# 01-SOM.net
KiCad netlist of a schematic drawn in Altium Designer
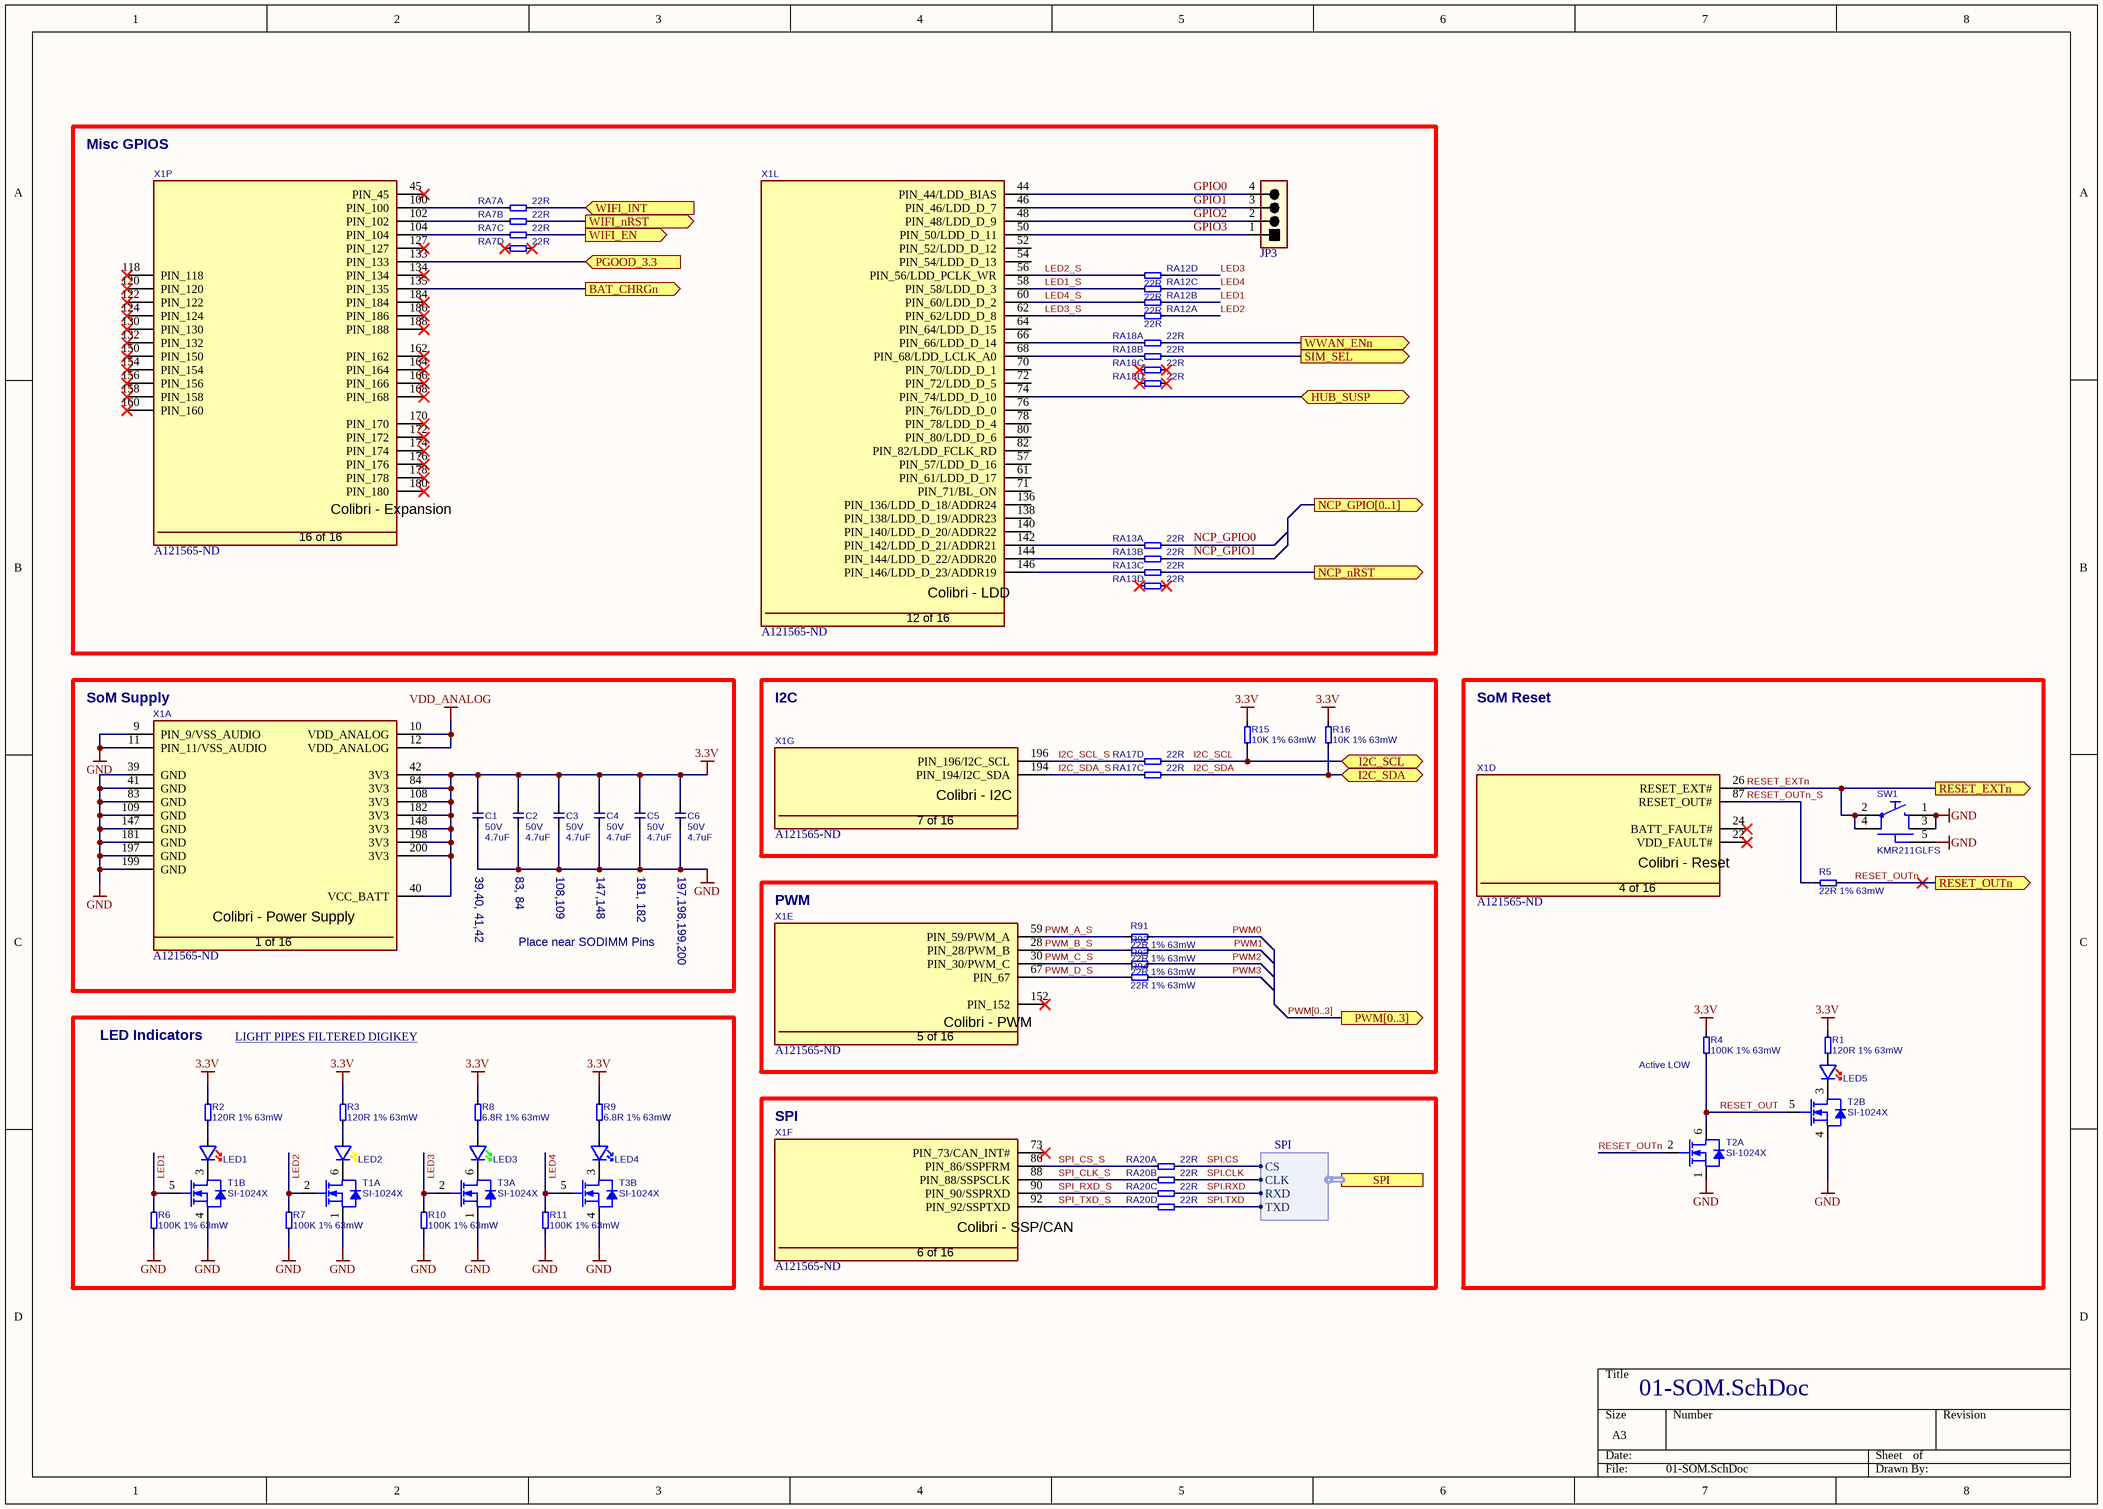
[diagram p0: 01-SOM.SchDoc]

(export (version "E")
  (design (tool "Eeschema 10.0.6"))
  (components
    (comp (ref "C1")
      (value "4.7uF")
      (footprint "T_CAPC1206X180N")
      (description "Capacitor Ceramic X7R 4.7uF 50V 20% 1206")
      (fields
        (field (name "TOLERANCE") "10%")
        (field (name "RATING") "50V")
        (field (name "Comment") "4.7uF 50V 20% X7R")
      )
      (libsource (lib "AI Gateway - Carrier") (part "C-4.7uF-50V-20%-1210"))
    )
    (comp (ref "C2")
      (value "4.7uF")
      (footprint "T_CAPC1206X180N")
      (description "Capacitor Ceramic X7R 4.7uF 50V 20% 1206")
      (fields
        (field (name "TOLERANCE") "10%")
        (field (name "RATING") "50V")
        (field (name "Comment") "4.7uF 50V 20% X7R")
      )
      (libsource (lib "AI Gateway - Carrier") (part "C-4.7uF-50V-20%-1210"))
    )
    (comp (ref "C3")
      (value "4.7uF")
      (footprint "T_CAPC1206X180N")
      (description "Capacitor Ceramic X7R 4.7uF 50V 20% 1206")
      (fields
        (field (name "TOLERANCE") "10%")
        (field (name "RATING") "50V")
        (field (name "Comment") "4.7uF 50V 20% X7R")
      )
      (libsource (lib "AI Gateway - Carrier") (part "C-4.7uF-50V-20%-1210"))
    )
    (comp (ref "C4")
      (value "4.7uF")
      (footprint "T_CAPC1206X180N")
      (description "Capacitor Ceramic X7R 4.7uF 50V 20% 1206")
      (fields
        (field (name "TOLERANCE") "10%")
        (field (name "RATING") "50V")
        (field (name "Comment") "4.7uF 50V 20% X7R")
      )
      (libsource (lib "AI Gateway - Carrier") (part "C-4.7uF-50V-20%-1210"))
    )
    (comp (ref "C5")
      (value "4.7uF")
      (footprint "T_CAPC1206X180N")
      (description "Capacitor Ceramic X7R 4.7uF 50V 20% 1206")
      (fields
        (field (name "TOLERANCE") "10%")
        (field (name "RATING") "50V")
        (field (name "Comment") "4.7uF 50V 20% X7R")
      )
      (libsource (lib "AI Gateway - Carrier") (part "C-4.7uF-50V-20%-1210"))
    )
    (comp (ref "C6")
      (value "4.7uF")
      (footprint "T_CAPC1206X180N")
      (description "Capacitor Ceramic X7R 4.7uF 50V 20% 1206")
      (fields
        (field (name "TOLERANCE") "10%")
        (field (name "RATING") "50V")
        (field (name "Comment") "4.7uF 50V 20% X7R")
      )
      (libsource (lib "AI Gateway - Carrier") (part "C-4.7uF-50V-20%-1210"))
    )
    (comp (ref "JP3")
      (value "61300411121")
      (footprint "Header 1x4, 2.54mm pitch, male")
      (description "Header male, 1x4 Pins, 2.54 mm pitch")
      (fields (field (name "MFG") "Würth Elektronik"))
      (libsource (lib "AI Gateway - Carrier") (part "Header 1x4"))
    )
    (comp (ref "LED1")
      (value "150060RS75000")
      (footprint "LEDC1608X80N")
      (description "Red 625nm LED Indication - Discrete 2V 0603 (1608 Metric)")
      (fields (field (name "MFG") "Würth Elektronik"))
      (libsource (lib "AI Gateway - Carrier") (part "LED-RED-0603"))
    )
    (comp (ref "LED2")
      (value "150060YS75000")
      (footprint "LEDC1608X80N")
      (description "Yellow 590nm LED Indication - Discrete 2V 0603 (1608 Metric)")
      (fields (field (name "MFG") "Würth Elektronik"))
      (libsource (lib "AI Gateway - Carrier") (part "LED-YELLOW-0603"))
    )
    (comp (ref "LED3")
      (value "150060GS75000")
      (footprint "LEDC1608X80N")
      (description "Green 520nm LED Indication - Discrete 3.2V 0603 (1608 Metric)")
      (fields (field (name "MFG") "Würth Elektronik"))
      (libsource (lib "AI Gateway - Carrier") (part "LED-GREEN-0603"))
    )
    (comp (ref "LED4")
      (value "150060BS75000")
      (footprint "LEDC1608X80N")
      (description "Blue 470nm LED Indication - Discrete 3.2V 0603 (1608 Metric)")
      (fields (field (name "MFG") "Würth Elektronik"))
      (libsource (lib "AI Gateway - Carrier") (part "LED-BLUE-0603"))
    )
    (comp (ref "LED5")
      (value "150060RS75000")
      (footprint "LEDC1608X80N")
      (description "Red 625nm LED Indication - Discrete 2V 0603 (1608 Metric)")
      (fields (field (name "MFG") "Würth Elektronik"))
      (libsource (lib "AI Gateway - Carrier") (part "LED-RED-0603"))
    )
    (comp (ref "R1")
      (value "120R 1% 63mW")
      (footprint "RESC1005X40N")
      (description "Resistor 120ohm 63mW 1% 0402")
      (fields (field (name "POWER") "63mW") (field (name "TOLERANCE") "1%"))
      (libsource (lib "AI Gateway - Carrier") (part "R-120R-1%-0402"))
    )
    (comp (ref "R2")
      (value "120R 1% 63mW")
      (footprint "RESC1005X40N")
      (description "Resistor 120ohm 63mW 1% 0402")
      (fields (field (name "POWER") "63mW") (field (name "TOLERANCE") "1%"))
      (libsource (lib "AI Gateway - Carrier") (part "R-120R-1%-0402"))
    )
    (comp (ref "R3")
      (value "120R 1% 63mW")
      (footprint "RESC1005X40N")
      (description "Resistor 120ohm 63mW 1% 0402")
      (fields (field (name "POWER") "63mW") (field (name "TOLERANCE") "1%"))
      (libsource (lib "AI Gateway - Carrier") (part "R-120R-1%-0402"))
    )
    (comp (ref "R4")
      (value "100K 1% 63mW")
      (footprint "RESC1005X40N")
      (description "Resistor 100Kohm 63mW 1% 0402")
      (fields (field (name "POWER") "63mW") (field (name "TOLERANCE") "1%"))
      (libsource (lib "AI Gateway - Carrier") (part "R-100K-1%-0402"))
    )
    (comp (ref "R5")
      (value "22R 1% 63mW")
      (footprint "RESC1005X40N")
      (description "Resistor 22ohm 63mW 1% 0402")
      (fields (field (name "POWER") "63mW") (field (name "TOLERANCE") "1%"))
      (libsource (lib "AI Gateway - Carrier") (part "R-22R-1%-0402"))
    )
    (comp (ref "R6")
      (value "100K 1% 63mW")
      (footprint "RESC1005X40N")
      (description "Resistor 100Kohm 63mW 1% 0402")
      (fields (field (name "TOLERANCE") "1%") (field (name "POWER") "63mW"))
      (libsource (lib "AI Gateway - Carrier") (part "R-100K-1%-0402"))
    )
    (comp (ref "R7")
      (value "100K 1% 63mW")
      (footprint "RESC1005X40N")
      (description "Resistor 100Kohm 63mW 1% 0402")
      (fields (field (name "TOLERANCE") "1%") (field (name "POWER") "63mW"))
      (libsource (lib "AI Gateway - Carrier") (part "R-100K-1%-0402"))
    )
    (comp (ref "R8")
      (value "6.8R 1% 63mW")
      (footprint "RESC1005X40N")
      (description "Resistor 6.8ohm 63mW 1% 0402")
      (fields (field (name "POWER") "63mW") (field (name "TOLERANCE") "1%"))
      (libsource (lib "AI Gateway - Carrier") (part "R-6.8R-1%-0402"))
    )
    (comp (ref "R9")
      (value "6.8R 1% 63mW")
      (footprint "RESC1005X40N")
      (description "Resistor 6.8ohm 63mW 1% 0402")
      (fields (field (name "POWER") "63mW") (field (name "TOLERANCE") "1%"))
      (libsource (lib "AI Gateway - Carrier") (part "R-6.8R-1%-0402"))
    )
    (comp (ref "R10")
      (value "100K 1% 63mW")
      (footprint "RESC1005X40N")
      (description "Resistor 100Kohm 63mW 1% 0402")
      (fields (field (name "TOLERANCE") "1%") (field (name "POWER") "63mW"))
      (libsource (lib "AI Gateway - Carrier") (part "R-100K-1%-0402"))
    )
    (comp (ref "R11")
      (value "100K 1% 63mW")
      (footprint "RESC1005X40N")
      (description "Resistor 100Kohm 63mW 1% 0402")
      (fields (field (name "TOLERANCE") "1%") (field (name "POWER") "63mW"))
      (libsource (lib "AI Gateway - Carrier") (part "R-100K-1%-0402"))
    )
    (comp (ref "R15")
      (value "10K 1% 63mW")
      (footprint "RESC1005X40N")
      (description "Resistor 10Kohm 63mW 1% 0402")
      (fields (field (name "POWER") "63mW") (field (name "TOLERANCE") "1%"))
      (libsource (lib "AI Gateway - Carrier") (part "R-10K-1%-0402"))
    )
    (comp (ref "R16")
      (value "10K 1% 63mW")
      (footprint "RESC1005X40N")
      (description "Resistor 10Kohm 63mW 1% 0402")
      (fields (field (name "POWER") "63mW") (field (name "TOLERANCE") "1%"))
      (libsource (lib "AI Gateway - Carrier") (part "R-10K-1%-0402"))
    )
    (comp (ref "R91")
      (value "22R 1% 63mW")
      (footprint "RESC1005X40N")
      (description "Resistor 22ohm 63mW 1% 0402")
      (fields (field (name "POWER") "63mW") (field (name "TOLERANCE") "1%"))
      (libsource (lib "AI Gateway - Carrier") (part "R-22R-1%-0402"))
    )
    (comp (ref "R92")
      (value "22R 1% 63mW")
      (footprint "RESC1005X40N")
      (description "Resistor 22ohm 63mW 1% 0402")
      (fields (field (name "POWER") "63mW") (field (name "TOLERANCE") "1%"))
      (libsource (lib "AI Gateway - Carrier") (part "R-22R-1%-0402"))
    )
    (comp (ref "R93")
      (value "22R 1% 63mW")
      (footprint "RESC1005X40N")
      (description "Resistor 22ohm 63mW 1% 0402")
      (fields (field (name "POWER") "63mW") (field (name "TOLERANCE") "1%"))
      (libsource (lib "AI Gateway - Carrier") (part "R-22R-1%-0402"))
    )
    (comp (ref "R94")
      (value "22R 1% 63mW")
      (footprint "RESC1005X40N")
      (description "Resistor 22ohm 63mW 1% 0402")
      (fields (field (name "POWER") "63mW") (field (name "TOLERANCE") "1%"))
      (libsource (lib "AI Gateway - Carrier") (part "R-22R-1%-0402"))
    )
    (comp (ref "RA7")
      (value "22R")
      (footprint "T_Resistor_Array_X4")
      (description "Resistor Array 22 R 63mW 5% 1206")
      (fields (field (name "TOLERANCE") "5%") (field (name "MFG") "Generic"))
      (libsource (lib "Passive") (part "RA-22R-5%-1206-div"))
    )
    (comp (ref "RA12")
      (value "22R")
      (footprint "T_Resistor_Array_X4")
      (description "Resistor Array 22 R 63mW 5% 1206")
      (fields (field (name "TOLERANCE") "5%") (field (name "MFG") "Generic"))
      (libsource (lib "Passive") (part "RA-22R-5%-1206-div"))
    )
    (comp (ref "RA13")
      (value "22R")
      (footprint "T_Resistor_Array_X4")
      (description "Resistor Array 22 R 63mW 5% 1206")
      (fields (field (name "TOLERANCE") "5%") (field (name "MFG") "Generic"))
      (libsource (lib "Passive") (part "RA-22R-5%-1206-div"))
    )
    (comp (ref "RA17")
      (value "22R")
      (footprint "T_Resistor_Array_X4")
      (description "Resistor Array 22 R 63mW 5% 1206")
      (fields (field (name "TOLERANCE") "5%") (field (name "MFG") "Generic"))
      (libsource (lib "Passive") (part "RA-22R-5%-1206-div"))
    )
    (comp (ref "RA18")
      (value "22R")
      (footprint "T_Resistor_Array_X4")
      (description "Resistor Array 22 R 63mW 5% 1206")
      (fields (field (name "TOLERANCE") "5%") (field (name "MFG") "Generic"))
      (libsource (lib "Passive") (part "RA-22R-5%-1206-div"))
    )
    (comp (ref "RA20")
      (value "22R")
      (footprint "T_Resistor_Array_X4")
      (description "Resistor Array 22 R 63mW 5% 1206")
      (fields (field (name "TOLERANCE") "5%") (field (name "MFG") "Generic"))
      (libsource (lib "Passive") (part "RA-22R-5%-1206-div"))
    )
    (comp (ref "SW1")
      (value "KMR211GLFS")
      (footprint "T_CnK_KMR211GLFS")
      (description "Power ON Switch")
      (fields (field (name "MFG") "C&N"))
      (libsource (lib "Passive") (part "SW-KMR211GLFS-1VA"))
    )
    (comp (ref "T1")
      (value "SI-1024X")
      (footprint "SOTFL50P160X60-6N")
      (description "Mosfet Array 2 N-Channel (Dual) 20V 485mA 250mW Surface Mount SC-89-6")
      (fields (field (name "MFG") "Vishay"))
      (libsource (lib "AI Gateway - Carrier") (part "T-Vishay-SI-1024X"))
    )
    (comp (ref "T2")
      (value "SI-1024X")
      (footprint "SOTFL50P160X60-6N")
      (description "Mosfet Array 2 N-Channel (Dual) 20V 485mA 250mW Surface Mount SC-89-6")
      (fields (field (name "MFG") "Vishay"))
      (libsource (lib "AI Gateway - Carrier") (part "T-Vishay-SI-1024X"))
    )
    (comp (ref "T3")
      (value "SI-1024X")
      (footprint "SOTFL50P160X60-6N")
      (description "Mosfet Array 2 N-Channel (Dual) 20V 485mA 250mW Surface Mount SC-89-6")
      (fields (field (name "MFG") "Vishay"))
      (libsource (lib "AI Gateway - Carrier") (part "T-Vishay-SI-1024X"))
    )
    (comp (ref "X1")
      (value "1473005-1")
      (footprint "T_Tyco_1473005-1")
      (description "SODIMM Connector")
      (fields (field (name "SUPPLIER PART NUMBER 1") "A121565-ND"))
      (libsource (lib "Connectors") (part "CON-Tyco-1473005-1-200-0.6mm"))
    )
  )
  (nets
    (net (code "2") (name "/BAT_CHRGn") (class "Default")
      (node (ref "X1") (pin "135") (pinfunction "PIN_135_135") (pintype "passive"))
    )
    (net (code "3") (name "/GPIO0") (class "Default")
      (node (ref "JP3") (pin "4") (pinfunction "4_4") (pintype "passive"))
      (node (ref "X1") (pin "44") (pinfunction "PIN_44/LDD_BIAS_44") (pintype "passive"))
    )
    (net (code "4") (name "/GPIO1") (class "Default")
      (node (ref "JP3") (pin "3") (pinfunction "3_3") (pintype "passive"))
      (node (ref "X1") (pin "46") (pinfunction "PIN_46/LDD_D_7_46") (pintype "passive"))
    )
    (net (code "5") (name "/GPIO2") (class "Default")
      (node (ref "JP3") (pin "2") (pinfunction "2_2") (pintype "passive"))
      (node (ref "X1") (pin "48") (pinfunction "PIN_48/LDD_D_9_48") (pintype "passive"))
    )
    (net (code "6") (name "/GPIO3") (class "Default")
      (node (ref "JP3") (pin "1") (pinfunction "1_1") (pintype "passive"))
      (node (ref "X1") (pin "50") (pinfunction "PIN_50/LDD_D_11_50") (pintype "passive"))
    )
    (net (code "7") (name "/HUB_SUSP") (class "Default")
      (node (ref "X1") (pin "74") (pinfunction "PIN_74/LDD_D_10_74") (pintype "passive"))
    )
    (net (code "8") (name "/I2C_SCL") (class "Default")
      (node (ref "R15") (pin "1") (pinfunction "1_1") (pintype "passive"))
      (node (ref "RA17") (pin "8") (pinfunction "8_8") (pintype "passive"))
    )
    (net (code "9") (name "/I2C_SCL_S") (class "Default")
      (node (ref "RA17") (pin "4") (pinfunction "4_4") (pintype "passive"))
      (node (ref "X1") (pin "196") (pinfunction "PIN_196/I2C_SCL_196") (pintype "passive"))
    )
    (net (code "10") (name "/I2C_SDA") (class "Default")
      (node (ref "R16") (pin "1") (pinfunction "1_1") (pintype "passive"))
      (node (ref "RA17") (pin "7") (pinfunction "7_7") (pintype "passive"))
    )
    (net (code "11") (name "/I2C_SDA_S") (class "Default")
      (node (ref "RA17") (pin "3") (pinfunction "3_3") (pintype "passive"))
      (node (ref "X1") (pin "194") (pinfunction "PIN_194/I2C_SDA_194") (pintype "passive"))
    )
    (net (code "12") (name "/LED1") (class "Default")
      (node (ref "R6") (pin "1") (pinfunction "1_1") (pintype "passive"))
      (node (ref "RA12") (pin "2") (pinfunction "2_2") (pintype "passive"))
      (node (ref "T1") (pin "5") (pinfunction "G_5") (pintype "passive"))
    )
    (net (code "13") (name "/LED1_S") (class "Default")
      (node (ref "RA12") (pin "7") (pinfunction "7_7") (pintype "passive"))
      (node (ref "X1") (pin "58") (pinfunction "PIN_58/LDD_D_3_58") (pintype "passive"))
    )
    (net (code "14") (name "/LED2") (class "Default")
      (node (ref "R7") (pin "1") (pinfunction "1_1") (pintype "passive"))
      (node (ref "RA12") (pin "1") (pinfunction "1_1") (pintype "passive"))
      (node (ref "T1") (pin "2") (pinfunction "G_2") (pintype "passive"))
    )
    (net (code "15") (name "/LED2_S") (class "Default")
      (node (ref "RA12") (pin "8") (pinfunction "8_8") (pintype "passive"))
      (node (ref "X1") (pin "56") (pinfunction "PIN_56/LDD_PCLK_WR_56") (pintype "passive"))
    )
    (net (code "16") (name "/LED3") (class "Default")
      (node (ref "R10") (pin "1") (pinfunction "1_1") (pintype "passive"))
      (node (ref "RA12") (pin "4") (pinfunction "4_4") (pintype "passive"))
      (node (ref "T3") (pin "2") (pinfunction "G_2") (pintype "passive"))
    )
    (net (code "17") (name "/LED3_S") (class "Default")
      (node (ref "RA12") (pin "5") (pinfunction "5_5") (pintype "passive"))
      (node (ref "X1") (pin "62") (pinfunction "PIN_62/LDD_D_8_62") (pintype "passive"))
    )
    (net (code "18") (name "/LED4") (class "Default")
      (node (ref "R11") (pin "1") (pinfunction "1_1") (pintype "passive"))
      (node (ref "RA12") (pin "3") (pinfunction "3_3") (pintype "passive"))
      (node (ref "T3") (pin "5") (pinfunction "G_5") (pintype "passive"))
    )
    (net (code "19") (name "/LED4_S") (class "Default")
      (node (ref "RA12") (pin "6") (pinfunction "6_6") (pintype "passive"))
      (node (ref "X1") (pin "60") (pinfunction "PIN_60/LDD_D_2_60") (pintype "passive"))
    )
    (net (code "20") (name "/NCP_GPIO0") (class "Default")
      (node (ref "RA13") (pin "5") (pinfunction "5_5") (pintype "passive"))
    )
    (net (code "21") (name "/NCP_GPIO1") (class "Default")
      (node (ref "RA13") (pin "6") (pinfunction "6_6") (pintype "passive"))
    )
    (net (code "23") (name "/NCP_nRST") (class "Default")
      (node (ref "RA13") (pin "7") (pinfunction "7_7") (pintype "passive"))
    )
    (net (code "24") (name "/PGOOD_3.3") (class "Default")
      (node (ref "X1") (pin "133") (pinfunction "PIN_133_133") (pintype "passive"))
    )
    (net (code "25") (name "/PWM0") (class "Default")
      (node (ref "R91") (pin "1") (pinfunction "1_1") (pintype "passive"))
    )
    (net (code "26") (name "/PWM1") (class "Default")
      (node (ref "R92") (pin "1") (pinfunction "1_1") (pintype "passive"))
    )
    (net (code "27") (name "/PWM2") (class "Default")
      (node (ref "R93") (pin "1") (pinfunction "1_1") (pintype "passive"))
    )
    (net (code "28") (name "/PWM3") (class "Default")
      (node (ref "R94") (pin "1") (pinfunction "1_1") (pintype "passive"))
    )
    (net (code "30") (name "/PWM_A_S") (class "Default")
      (node (ref "R91") (pin "2") (pinfunction "2_2") (pintype "passive"))
      (node (ref "X1") (pin "59") (pinfunction "PIN_59/PWM_A_59") (pintype "passive"))
    )
    (net (code "31") (name "/PWM_B_S") (class "Default")
      (node (ref "R92") (pin "2") (pinfunction "2_2") (pintype "passive"))
      (node (ref "X1") (pin "28") (pinfunction "PIN_28/PWM_B_28") (pintype "passive"))
    )
    (net (code "32") (name "/PWM_C_S") (class "Default")
      (node (ref "R93") (pin "2") (pinfunction "2_2") (pintype "passive"))
      (node (ref "X1") (pin "30") (pinfunction "PIN_30/PWM_C_30") (pintype "passive"))
    )
    (net (code "33") (name "/PWM_D_S") (class "Default")
      (node (ref "R94") (pin "2") (pinfunction "2_2") (pintype "passive"))
      (node (ref "X1") (pin "67") (pinfunction "PIN_67_67") (pintype "passive"))
    )
    (net (code "34") (name "/RESET_EXTn") (class "Default")
      (node (ref "SW1") (pin "2") (pinfunction "2_2") (pintype "passive"))
      (node (ref "SW1") (pin "4") (pinfunction "4_4") (pintype "passive"))
      (node (ref "X1") (pin "26") (pinfunction "RESET_EXT#_26") (pintype "passive"))
    )
    (net (code "35") (name "/RESET_OUT") (class "Default")
      (node (ref "R4") (pin "1") (pinfunction "1_1") (pintype "passive"))
      (node (ref "T2") (pin "5") (pinfunction "G_5") (pintype "passive"))
      (node (ref "T2") (pin "6") (pinfunction "D_6") (pintype "passive"))
    )
    (net (code "36") (name "/RESET_OUTn") (class "Default")
      (node (ref "R5") (pin "1") (pinfunction "1_1") (pintype "passive"))
      (node (ref "T2") (pin "2") (pinfunction "G_2") (pintype "passive"))
    )
    (net (code "37") (name "/RESET_OUTn_S") (class "Default")
      (node (ref "R5") (pin "2") (pinfunction "2_2") (pintype "passive"))
      (node (ref "X1") (pin "87") (pinfunction "RESET_OUT#_87") (pintype "passive"))
    )
    (net (code "38") (name "/SIM_SEL") (class "Default")
      (node (ref "RA18") (pin "6") (pinfunction "6_6") (pintype "passive"))
    )
    (net (code "39") (name "/SPI.CLK") (class "Default")
      (node (ref "RA20") (pin "6") (pinfunction "6_6") (pintype "passive"))
    )
    (net (code "40") (name "/SPI.CS") (class "Default")
      (node (ref "RA20") (pin "5") (pinfunction "5_5") (pintype "passive"))
    )
    (net (code "41") (name "/SPI.RXD") (class "Default")
      (node (ref "RA20") (pin "7") (pinfunction "7_7") (pintype "passive"))
    )
    (net (code "42") (name "/SPI.TXD") (class "Default")
      (node (ref "RA20") (pin "8") (pinfunction "8_8") (pintype "passive"))
    )
    (net (code "43") (name "/SPI_CLK_S") (class "Default")
      (node (ref "RA20") (pin "2") (pinfunction "2_2") (pintype "passive"))
      (node (ref "X1") (pin "88") (pinfunction "PIN_88/SSPSCLK_88") (pintype "passive"))
    )
    (net (code "44") (name "/SPI_CS_S") (class "Default")
      (node (ref "RA20") (pin "1") (pinfunction "1_1") (pintype "passive"))
      (node (ref "X1") (pin "86") (pinfunction "PIN_86/SSPFRM_86") (pintype "passive"))
    )
    (net (code "45") (name "/SPI_RXD_S") (class "Default")
      (node (ref "RA20") (pin "3") (pinfunction "3_3") (pintype "passive"))
      (node (ref "X1") (pin "90") (pinfunction "PIN_90/SSPRXD_90") (pintype "passive"))
    )
    (net (code "46") (name "/SPI_TXD_S") (class "Default")
      (node (ref "RA20") (pin "4") (pinfunction "4_4") (pintype "passive"))
      (node (ref "X1") (pin "92") (pinfunction "PIN_92/SSPTXD_92") (pintype "passive"))
    )
    (net (code "47") (name "/WIFI_EN") (class "Default")
      (node (ref "RA7") (pin "7") (pinfunction "7_7") (pintype "passive"))
    )
    (net (code "48") (name "/WIFI_INT") (class "Default")
      (node (ref "RA7") (pin "5") (pinfunction "5_5") (pintype "passive"))
    )
    (net (code "49") (name "/WIFI_nRST") (class "Default")
      (node (ref "RA7") (pin "6") (pinfunction "6_6") (pintype "passive"))
    )
    (net (code "50") (name "/WWAN_ENn") (class "Default")
      (node (ref "RA18") (pin "5") (pinfunction "5_5") (pintype "passive"))
    )
    (net (code "52") (name "3.3V") (class "Default")
      (node (ref "C1") (pin "2") (pinfunction "2_2") (pintype "passive"))
      (node (ref "C2") (pin "2") (pinfunction "2_2") (pintype "passive"))
      (node (ref "C3") (pin "2") (pinfunction "2_2") (pintype "passive"))
      (node (ref "C4") (pin "2") (pinfunction "2_2") (pintype "passive"))
      (node (ref "C5") (pin "2") (pinfunction "2_2") (pintype "passive"))
      (node (ref "C6") (pin "2") (pinfunction "2_2") (pintype "passive"))
      (node (ref "R1") (pin "2") (pinfunction "2_2") (pintype "passive"))
      (node (ref "R15") (pin "2") (pinfunction "2_2") (pintype "passive"))
      (node (ref "R16") (pin "2") (pinfunction "2_2") (pintype "passive"))
      (node (ref "R2") (pin "1") (pinfunction "1_1") (pintype "passive"))
      (node (ref "R3") (pin "1") (pinfunction "1_1") (pintype "passive"))
      (node (ref "R4") (pin "2") (pinfunction "2_2") (pintype "passive"))
      (node (ref "R8") (pin "1") (pinfunction "1_1") (pintype "passive"))
      (node (ref "R9") (pin "1") (pinfunction "1_1") (pintype "passive"))
      (node (ref "X1") (pin "108") (pinfunction "3V3_108") (pintype "passive"))
      (node (ref "X1") (pin "148") (pinfunction "3V3_148") (pintype "passive"))
      (node (ref "X1") (pin "182") (pinfunction "3V3_182") (pintype "power_in"))
      (node (ref "X1") (pin "198") (pinfunction "3V3_198") (pintype "power_in"))
      (node (ref "X1") (pin "200") (pinfunction "3V3_200") (pintype "power_in"))
      (node (ref "X1") (pin "40") (pinfunction "VCC_BATT_40") (pintype "power_in"))
      (node (ref "X1") (pin "42") (pinfunction "3V3_42") (pintype "power_in"))
      (node (ref "X1") (pin "84") (pinfunction "3V3_84") (pintype "power_in"))
    )
    (net (code "53") (name "GND") (class "Default")
      (node (ref "C1") (pin "1") (pinfunction "1_1") (pintype "passive"))
      (node (ref "C2") (pin "1") (pinfunction "1_1") (pintype "passive"))
      (node (ref "C3") (pin "1") (pinfunction "1_1") (pintype "passive"))
      (node (ref "C4") (pin "1") (pinfunction "1_1") (pintype "passive"))
      (node (ref "C5") (pin "1") (pinfunction "1_1") (pintype "passive"))
      (node (ref "C6") (pin "1") (pinfunction "1_1") (pintype "passive"))
      (node (ref "R10") (pin "2") (pinfunction "2_2") (pintype "passive"))
      (node (ref "R11") (pin "2") (pinfunction "2_2") (pintype "passive"))
      (node (ref "R6") (pin "2") (pinfunction "2_2") (pintype "passive"))
      (node (ref "R7") (pin "2") (pinfunction "2_2") (pintype "passive"))
      (node (ref "SW1") (pin "1") (pinfunction "1_1") (pintype "passive"))
      (node (ref "SW1") (pin "3") (pinfunction "3_3") (pintype "passive"))
      (node (ref "SW1") (pin "5") (pinfunction "5_5") (pintype "passive"))
      (node (ref "T1") (pin "1") (pinfunction "S_1") (pintype "passive"))
      (node (ref "T1") (pin "4") (pinfunction "S_4") (pintype "passive"))
      (node (ref "T2") (pin "1") (pinfunction "S_1") (pintype "passive"))
      (node (ref "T2") (pin "4") (pinfunction "S_4") (pintype "passive"))
      (node (ref "T3") (pin "1") (pinfunction "S_1") (pintype "passive"))
      (node (ref "T3") (pin "4") (pinfunction "S_4") (pintype "passive"))
      (node (ref "X1") (pin "109") (pinfunction "GND_109") (pintype "power_in"))
      (node (ref "X1") (pin "11") (pinfunction "PIN_11/VSS_AUDIO_11") (pintype "passive"))
      (node (ref "X1") (pin "147") (pinfunction "GND_147") (pintype "power_in"))
      (node (ref "X1") (pin "181") (pinfunction "GND_181") (pintype "power_in"))
      (node (ref "X1") (pin "197") (pinfunction "GND_197") (pintype "power_in"))
      (node (ref "X1") (pin "199") (pinfunction "GND_199") (pintype "power_in"))
      (node (ref "X1") (pin "39") (pinfunction "GND_39") (pintype "power_in"))
      (node (ref "X1") (pin "41") (pinfunction "GND_41") (pintype "power_in"))
      (node (ref "X1") (pin "83") (pinfunction "GND_83") (pintype "power_in"))
      (node (ref "X1") (pin "9") (pinfunction "PIN_9/VSS_AUDIO_9") (pintype "passive"))
    )
    (net (code "54") (name "Net-(LED1-Pad2)") (class "Default")
      (node (ref "LED1") (pin "2") (pinfunction "2_2") (pintype "passive"))
      (node (ref "R2") (pin "2") (pinfunction "2_2") (pintype "passive"))
    )
    (net (code "55") (name "Net-(LED2-Pad2)") (class "Default")
      (node (ref "LED2") (pin "2") (pinfunction "2_2") (pintype "passive"))
      (node (ref "R3") (pin "2") (pinfunction "2_2") (pintype "passive"))
    )
    (net (code "56") (name "Net-(LED3-Pad2)") (class "Default")
      (node (ref "LED3") (pin "2") (pinfunction "2_2") (pintype "passive"))
      (node (ref "R8") (pin "2") (pinfunction "2_2") (pintype "passive"))
    )
    (net (code "57") (name "Net-(LED4-Pad2)") (class "Default")
      (node (ref "LED4") (pin "2") (pinfunction "2_2") (pintype "passive"))
      (node (ref "R9") (pin "2") (pinfunction "2_2") (pintype "passive"))
    )
    (net (code "58") (name "Net-(LED5-Pad2)") (class "Default")
      (node (ref "LED5") (pin "2") (pinfunction "2_2") (pintype "passive"))
      (node (ref "R1") (pin "1") (pinfunction "1_1") (pintype "passive"))
    )
    (net (code "59") (name "Net-(T1A-D)") (class "Default")
      (node (ref "LED2") (pin "1") (pinfunction "1_1") (pintype "passive"))
      (node (ref "T1") (pin "6") (pinfunction "D_6") (pintype "passive"))
    )
    (net (code "60") (name "Net-(T1B-D)") (class "Default")
      (node (ref "LED1") (pin "1") (pinfunction "1_1") (pintype "passive"))
      (node (ref "T1") (pin "3") (pinfunction "D_3") (pintype "passive"))
    )
    (net (code "61") (name "Net-(T2B-D)") (class "Default")
      (node (ref "LED5") (pin "1") (pinfunction "1_1") (pintype "passive"))
      (node (ref "T2") (pin "3") (pinfunction "D_3") (pintype "passive"))
    )
    (net (code "62") (name "Net-(T3A-D)") (class "Default")
      (node (ref "LED3") (pin "1") (pinfunction "1_1") (pintype "passive"))
      (node (ref "T3") (pin "6") (pinfunction "D_6") (pintype "passive"))
    )
    (net (code "63") (name "Net-(T3B-D)") (class "Default")
      (node (ref "LED4") (pin "1") (pinfunction "1_1") (pintype "passive"))
      (node (ref "T3") (pin "3") (pinfunction "D_3") (pintype "passive"))
    )
    (net (code "64") (name "Net-(X1L-PIN_66{slash}LDD_D_14)") (class "Default")
      (node (ref "RA18") (pin "1") (pinfunction "1_1") (pintype "passive"))
      (node (ref "X1") (pin "66") (pinfunction "PIN_66/LDD_D_14_66") (pintype "passive"))
    )
    (net (code "65") (name "Net-(X1L-PIN_68{slash}LDD_LCLK_A0)") (class "Default")
      (node (ref "RA18") (pin "2") (pinfunction "2_2") (pintype "passive"))
      (node (ref "X1") (pin "68") (pinfunction "PIN_68/LDD_LCLK_A0_68") (pintype "passive"))
    )
    (net (code "66") (name "Net-(X1L-PIN_142{slash}LDD_D_21{slash}ADDR21)") (class "Default")
      (node (ref "RA13") (pin "1") (pinfunction "1_1") (pintype "passive"))
      (node (ref "X1") (pin "142") (pinfunction "PIN_142/LDD_D_21/ADDR21_142") (pintype "passive"))
    )
    (net (code "67") (name "Net-(X1L-PIN_144{slash}LDD_D_22{slash}ADDR20)") (class "Default")
      (node (ref "RA13") (pin "2") (pinfunction "2_2") (pintype "passive"))
      (node (ref "X1") (pin "144") (pinfunction "PIN_144/LDD_D_22/ADDR20_144") (pintype "passive"))
    )
    (net (code "68") (name "Net-(X1L-PIN_146{slash}LDD_D_23{slash}ADDR19)") (class "Default")
      (node (ref "RA13") (pin "3") (pinfunction "3_3") (pintype "passive"))
      (node (ref "X1") (pin "146") (pinfunction "PIN_146/LDD_D_23/ADDR19_146") (pintype "passive"))
    )
    (net (code "69") (name "Net-(X1P-PIN_100)") (class "Default")
      (node (ref "RA7") (pin "1") (pinfunction "1_1") (pintype "passive"))
      (node (ref "X1") (pin "100") (pinfunction "PIN_100_100") (pintype "passive"))
    )
    (net (code "70") (name "Net-(X1P-PIN_102)") (class "Default")
      (node (ref "RA7") (pin "2") (pinfunction "2_2") (pintype "passive"))
      (node (ref "X1") (pin "102") (pinfunction "PIN_102_102") (pintype "passive"))
    )
    (net (code "71") (name "Net-(X1P-PIN_104)") (class "Default")
      (node (ref "RA7") (pin "3") (pinfunction "3_3") (pintype "passive"))
      (node (ref "X1") (pin "104") (pinfunction "PIN_104_104") (pintype "passive"))
    )
    (net (code "72") (name "VDD_ANALOG") (class "Default")
      (node (ref "X1") (pin "10") (pinfunction "VDD_ANALOG_10") (pintype "passive"))
      (node (ref "X1") (pin "12") (pinfunction "VDD_ANALOG_12") (pintype "passive"))
    )
    (net (code "73") (name "unconnected-(RA7-Pad4)") (class "Default")
      (node (ref "RA7") (pin "4") (pinfunction "4_4") (pintype "passive+no_connect"))
    )
    (net (code "74") (name "unconnected-(RA7-Pad8)") (class "Default")
      (node (ref "RA7") (pin "8") (pinfunction "8_8") (pintype "passive+no_connect"))
    )
    (net (code "75") (name "unconnected-(RA13-Pad4)") (class "Default")
      (node (ref "RA13") (pin "4") (pinfunction "4_4") (pintype "passive+no_connect"))
    )
    (net (code "76") (name "unconnected-(RA13-Pad8)") (class "Default")
      (node (ref "RA13") (pin "8") (pinfunction "8_8") (pintype "passive+no_connect"))
    )
    (net (code "77") (name "unconnected-(RA18-Pad3)") (class "Default")
      (node (ref "RA18") (pin "3") (pinfunction "3_3") (pintype "passive+no_connect"))
    )
    (net (code "78") (name "unconnected-(RA18-Pad4)") (class "Default")
      (node (ref "RA18") (pin "4") (pinfunction "4_4") (pintype "passive+no_connect"))
    )
    (net (code "79") (name "unconnected-(RA18-Pad7)") (class "Default")
      (node (ref "RA18") (pin "7") (pinfunction "7_7") (pintype "passive+no_connect"))
    )
    (net (code "80") (name "unconnected-(RA18-Pad8)") (class "Default")
      (node (ref "RA18") (pin "8") (pinfunction "8_8") (pintype "passive+no_connect"))
    )
    (net (code "81") (name "unconnected-(X1D-BATT_FAULT#-Pad24)") (class "Default")
      (node (ref "X1") (pin "24") (pinfunction "BATT_FAULT#_24") (pintype "passive+no_connect"))
    )
    (net (code "82") (name "unconnected-(X1D-VDD_FAULT#-Pad22)") (class "Default")
      (node (ref "X1") (pin "22") (pinfunction "VDD_FAULT#_22") (pintype "passive+no_connect"))
    )
    (net (code "83") (name "unconnected-(X1E-PIN_152-Pad152)") (class "Default")
      (node (ref "X1") (pin "152") (pinfunction "PIN_152_152") (pintype "passive+no_connect"))
    )
    (net (code "84") (name "unconnected-(X1F-PIN_73{slash}CAN_INT#-Pad73)") (class "Default")
      (node (ref "X1") (pin "73") (pinfunction "PIN_73/CAN_INT#_73") (pintype "passive+no_connect"))
    )
    (net (code "85") (name "unconnected-(X1L-PIN_52{slash}LDD_D_12-Pad52)") (class "Default")
      (node (ref "X1") (pin "52") (pinfunction "PIN_52/LDD_D_12_52") (pintype "passive"))
    )
    (net (code "86") (name "unconnected-(X1L-PIN_54{slash}LDD_D_13-Pad54)") (class "Default")
      (node (ref "X1") (pin "54") (pinfunction "PIN_54/LDD_D_13_54") (pintype "passive"))
    )
    (net (code "87") (name "unconnected-(X1L-PIN_57{slash}LDD_D_16-Pad57)") (class "Default")
      (node (ref "X1") (pin "57") (pinfunction "PIN_57/LDD_D_16_57") (pintype "passive"))
    )
    (net (code "88") (name "unconnected-(X1L-PIN_61{slash}LDD_D_17-Pad61)") (class "Default")
      (node (ref "X1") (pin "61") (pinfunction "PIN_61/LDD_D_17_61") (pintype "passive"))
    )
    (net (code "89") (name "unconnected-(X1L-PIN_64{slash}LDD_D_15-Pad64)") (class "Default")
      (node (ref "X1") (pin "64") (pinfunction "PIN_64/LDD_D_15_64") (pintype "passive"))
    )
    (net (code "90") (name "unconnected-(X1L-PIN_70{slash}LDD_D_1-Pad70)") (class "Default")
      (node (ref "X1") (pin "70") (pinfunction "PIN_70/LDD_D_1_70") (pintype "passive"))
    )
    (net (code "91") (name "unconnected-(X1L-PIN_71{slash}BL_ON-Pad71)") (class "Default")
      (node (ref "X1") (pin "71") (pinfunction "PIN_71/BL_ON_71") (pintype "passive"))
    )
    (net (code "92") (name "unconnected-(X1L-PIN_72{slash}LDD_D_5-Pad72)") (class "Default")
      (node (ref "X1") (pin "72") (pinfunction "PIN_72/LDD_D_5_72") (pintype "passive"))
    )
    (net (code "93") (name "unconnected-(X1L-PIN_76{slash}LDD_D_0-Pad76)") (class "Default")
      (node (ref "X1") (pin "76") (pinfunction "PIN_76/LDD_D_0_76") (pintype "passive"))
    )
    (net (code "94") (name "unconnected-(X1L-PIN_78{slash}LDD_D_4-Pad78)") (class "Default")
      (node (ref "X1") (pin "78") (pinfunction "PIN_78/LDD_D_4_78") (pintype "passive"))
    )
    (net (code "95") (name "unconnected-(X1L-PIN_80{slash}LDD_D_6-Pad80)") (class "Default")
      (node (ref "X1") (pin "80") (pinfunction "PIN_80/LDD_D_6_80") (pintype "passive"))
    )
    (net (code "96") (name "unconnected-(X1L-PIN_82{slash}LDD_FCLK_RD-Pad82)") (class "Default")
      (node (ref "X1") (pin "82") (pinfunction "PIN_82/LDD_FCLK_RD_82") (pintype "passive"))
    )
    (net (code "97") (name "unconnected-(X1L-PIN_136{slash}LDD_D_18{slash}ADDR24-Pad136)") (class "Default")
      (node (ref "X1") (pin "136") (pinfunction "PIN_136/LDD_D_18/ADDR24_136") (pintype "passive"))
    )
    (net (code "98") (name "unconnected-(X1L-PIN_138{slash}LDD_D_19{slash}ADDR23-Pad138)") (class "Default")
      (node (ref "X1") (pin "138") (pinfunction "PIN_138/LDD_D_19/ADDR23_138") (pintype "passive"))
    )
    (net (code "99") (name "unconnected-(X1L-PIN_140{slash}LDD_D_20{slash}ADDR22-Pad140)") (class "Default")
      (node (ref "X1") (pin "140") (pinfunction "PIN_140/LDD_D_20/ADDR22_140") (pintype "passive"))
    )
    (net (code "100") (name "unconnected-(X1P-PIN_45-Pad45)") (class "Default")
      (node (ref "X1") (pin "45") (pinfunction "PIN_45_45") (pintype "passive+no_connect"))
    )
    (net (code "101") (name "unconnected-(X1P-PIN_118-Pad118)") (class "Default")
      (node (ref "X1") (pin "118") (pinfunction "PIN_118_118") (pintype "passive+no_connect"))
    )
    (net (code "102") (name "unconnected-(X1P-PIN_120-Pad120)") (class "Default")
      (node (ref "X1") (pin "120") (pinfunction "PIN_120_120") (pintype "passive+no_connect"))
    )
    (net (code "103") (name "unconnected-(X1P-PIN_122-Pad122)") (class "Default")
      (node (ref "X1") (pin "122") (pinfunction "PIN_122_122") (pintype "passive+no_connect"))
    )
    (net (code "104") (name "unconnected-(X1P-PIN_124-Pad124)") (class "Default")
      (node (ref "X1") (pin "124") (pinfunction "PIN_124_124") (pintype "passive+no_connect"))
    )
    (net (code "105") (name "unconnected-(X1P-PIN_127-Pad127)") (class "Default")
      (node (ref "X1") (pin "127") (pinfunction "PIN_127_127") (pintype "passive+no_connect"))
    )
    (net (code "106") (name "unconnected-(X1P-PIN_130-Pad130)") (class "Default")
      (node (ref "X1") (pin "130") (pinfunction "PIN_130_130") (pintype "passive+no_connect"))
    )
    (net (code "107") (name "unconnected-(X1P-PIN_132-Pad132)") (class "Default")
      (node (ref "X1") (pin "132") (pinfunction "PIN_132_132") (pintype "passive+no_connect"))
    )
    (net (code "108") (name "unconnected-(X1P-PIN_134-Pad134)") (class "Default")
      (node (ref "X1") (pin "134") (pinfunction "PIN_134_134") (pintype "passive+no_connect"))
    )
    (net (code "109") (name "unconnected-(X1P-PIN_150-Pad150)") (class "Default")
      (node (ref "X1") (pin "150") (pinfunction "PIN_150_150") (pintype "passive+no_connect"))
    )
    (net (code "110") (name "unconnected-(X1P-PIN_154-Pad154)") (class "Default")
      (node (ref "X1") (pin "154") (pinfunction "PIN_154_154") (pintype "passive+no_connect"))
    )
    (net (code "111") (name "unconnected-(X1P-PIN_156-Pad156)") (class "Default")
      (node (ref "X1") (pin "156") (pinfunction "PIN_156_156") (pintype "passive+no_connect"))
    )
    (net (code "112") (name "unconnected-(X1P-PIN_158-Pad158)") (class "Default")
      (node (ref "X1") (pin "158") (pinfunction "PIN_158_158") (pintype "passive+no_connect"))
    )
    (net (code "113") (name "unconnected-(X1P-PIN_160-Pad160)") (class "Default")
      (node (ref "X1") (pin "160") (pinfunction "PIN_160_160") (pintype "passive+no_connect"))
    )
    (net (code "114") (name "unconnected-(X1P-PIN_162-Pad162)") (class "Default")
      (node (ref "X1") (pin "162") (pinfunction "PIN_162_162") (pintype "passive+no_connect"))
    )
    (net (code "115") (name "unconnected-(X1P-PIN_164-Pad164)") (class "Default")
      (node (ref "X1") (pin "164") (pinfunction "PIN_164_164") (pintype "passive+no_connect"))
    )
    (net (code "116") (name "unconnected-(X1P-PIN_166-Pad166)") (class "Default")
      (node (ref "X1") (pin "166") (pinfunction "PIN_166_166") (pintype "passive+no_connect"))
    )
    (net (code "117") (name "unconnected-(X1P-PIN_168-Pad168)") (class "Default")
      (node (ref "X1") (pin "168") (pinfunction "PIN_168_168") (pintype "passive+no_connect"))
    )
    (net (code "118") (name "unconnected-(X1P-PIN_170-Pad170)") (class "Default")
      (node (ref "X1") (pin "170") (pinfunction "PIN_170_170") (pintype "passive+no_connect"))
    )
    (net (code "119") (name "unconnected-(X1P-PIN_172-Pad172)") (class "Default")
      (node (ref "X1") (pin "172") (pinfunction "PIN_172_172") (pintype "passive+no_connect"))
    )
    (net (code "120") (name "unconnected-(X1P-PIN_174-Pad174)") (class "Default")
      (node (ref "X1") (pin "174") (pinfunction "PIN_174_174") (pintype "passive+no_connect"))
    )
    (net (code "121") (name "unconnected-(X1P-PIN_176-Pad176)") (class "Default")
      (node (ref "X1") (pin "176") (pinfunction "PIN_176_176") (pintype "passive+no_connect"))
    )
    (net (code "122") (name "unconnected-(X1P-PIN_178-Pad178)") (class "Default")
      (node (ref "X1") (pin "178") (pinfunction "PIN_178_178") (pintype "passive+no_connect"))
    )
    (net (code "123") (name "unconnected-(X1P-PIN_180-Pad180)") (class "Default")
      (node (ref "X1") (pin "180") (pinfunction "PIN_180_180") (pintype "passive+no_connect"))
    )
    (net (code "124") (name "unconnected-(X1P-PIN_184-Pad184)") (class "Default")
      (node (ref "X1") (pin "184") (pinfunction "PIN_184_184") (pintype "passive+no_connect"))
    )
    (net (code "125") (name "unconnected-(X1P-PIN_186-Pad186)") (class "Default")
      (node (ref "X1") (pin "186") (pinfunction "PIN_186_186") (pintype "passive+no_connect"))
    )
    (net (code "126") (name "unconnected-(X1P-PIN_188-Pad188)") (class "Default")
      (node (ref "X1") (pin "188") (pinfunction "PIN_188_188") (pintype "passive+no_connect"))
    )
  )
)
